# layout.net
KiCad netlist of a schematic drawn in EAGLE
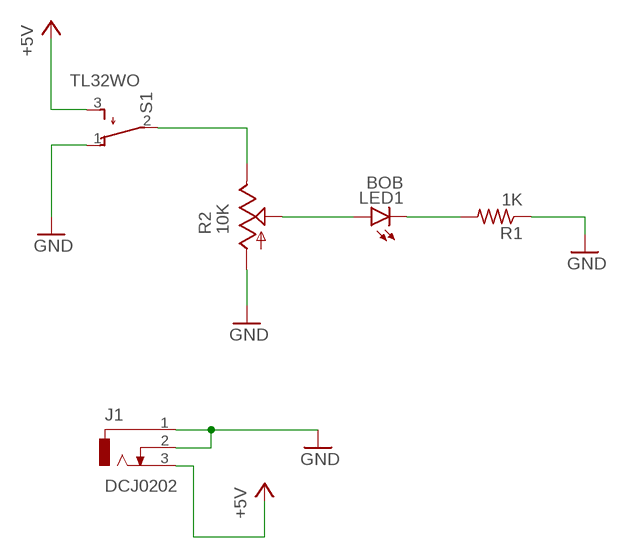
[diagram p0: schematic, sheet 1]

(export (version "E")
  (design (tool "Eeschema 10.0.6"))
  (components
    (comp (ref "J1")
      (value "DCJ0202")
      (footprint "eagle-import:DCJ0202")
      (libsource (lib "eagle-import") (part "DCJ0202"))
    )
    (comp (ref "LED1")
      (value "BOB")
      (footprint "eagle-import:LED5MM")
      (libsource (lib "eagle-import") (part "LED5MM"))
    )
    (comp (ref "R1")
      (value "1K")
      (footprint "eagle-import:0204_7")
      (libsource (lib "eagle-import") (part "R-US_0204/7"))
    )
    (comp (ref "R2")
      (value "10K")
      (footprint "eagle-import:RJ9W")
      (libsource (lib "eagle-import") (part "TRIM_US-RJ9W"))
    )
    (comp (ref "S1")
      (value "TL32WO")
      (footprint "eagle-import:TL3XWO")
      (libsource (lib "eagle-import") (part "TL32WO"))
    )
  )
  (nets
    (net (code "1") (name "+5V") (class "Default")
      (node (ref "J1") (pin "3") (pinfunction "3_3") (pintype "passive"))
      (node (ref "S1") (pin "3") (pinfunction "S_3") (pintype "passive"))
    )
    (net (code "2") (name "GND") (class "Default")
      (node (ref "J1") (pin "1") (pinfunction "1_1") (pintype "passive"))
      (node (ref "J1") (pin "2") (pinfunction "2_2") (pintype "passive"))
      (node (ref "R1") (pin "1") (pinfunction "1_1") (pintype "passive"))
      (node (ref "R2") (pin "A") (pinfunction "A_A") (pintype "passive"))
      (node (ref "S1") (pin "1") (pinfunction "O_1") (pintype "passive"))
    )
    (net (code "3") (name "Net-(LED1-C)") (class "Default")
      (node (ref "LED1") (pin "K") (pinfunction "C_K") (pintype "passive"))
      (node (ref "R1") (pin "2") (pinfunction "2_2") (pintype "passive"))
    )
    (net (code "4") (name "Net-(LED1-PadA)") (class "Default")
      (node (ref "LED1") (pin "A") (pinfunction "A_A") (pintype "passive"))
      (node (ref "R2") (pin "S") (pinfunction "S_S") (pintype "passive"))
    )
    (net (code "5") (name "Net-(S1-P)") (class "Default")
      (node (ref "R2") (pin "E") (pinfunction "E_E") (pintype "passive"))
      (node (ref "S1") (pin "2") (pinfunction "P_2") (pintype "passive"))
    )
  )
)
